# 1LFO.net
KiCad netlist of a schematic drawn in EAGLE
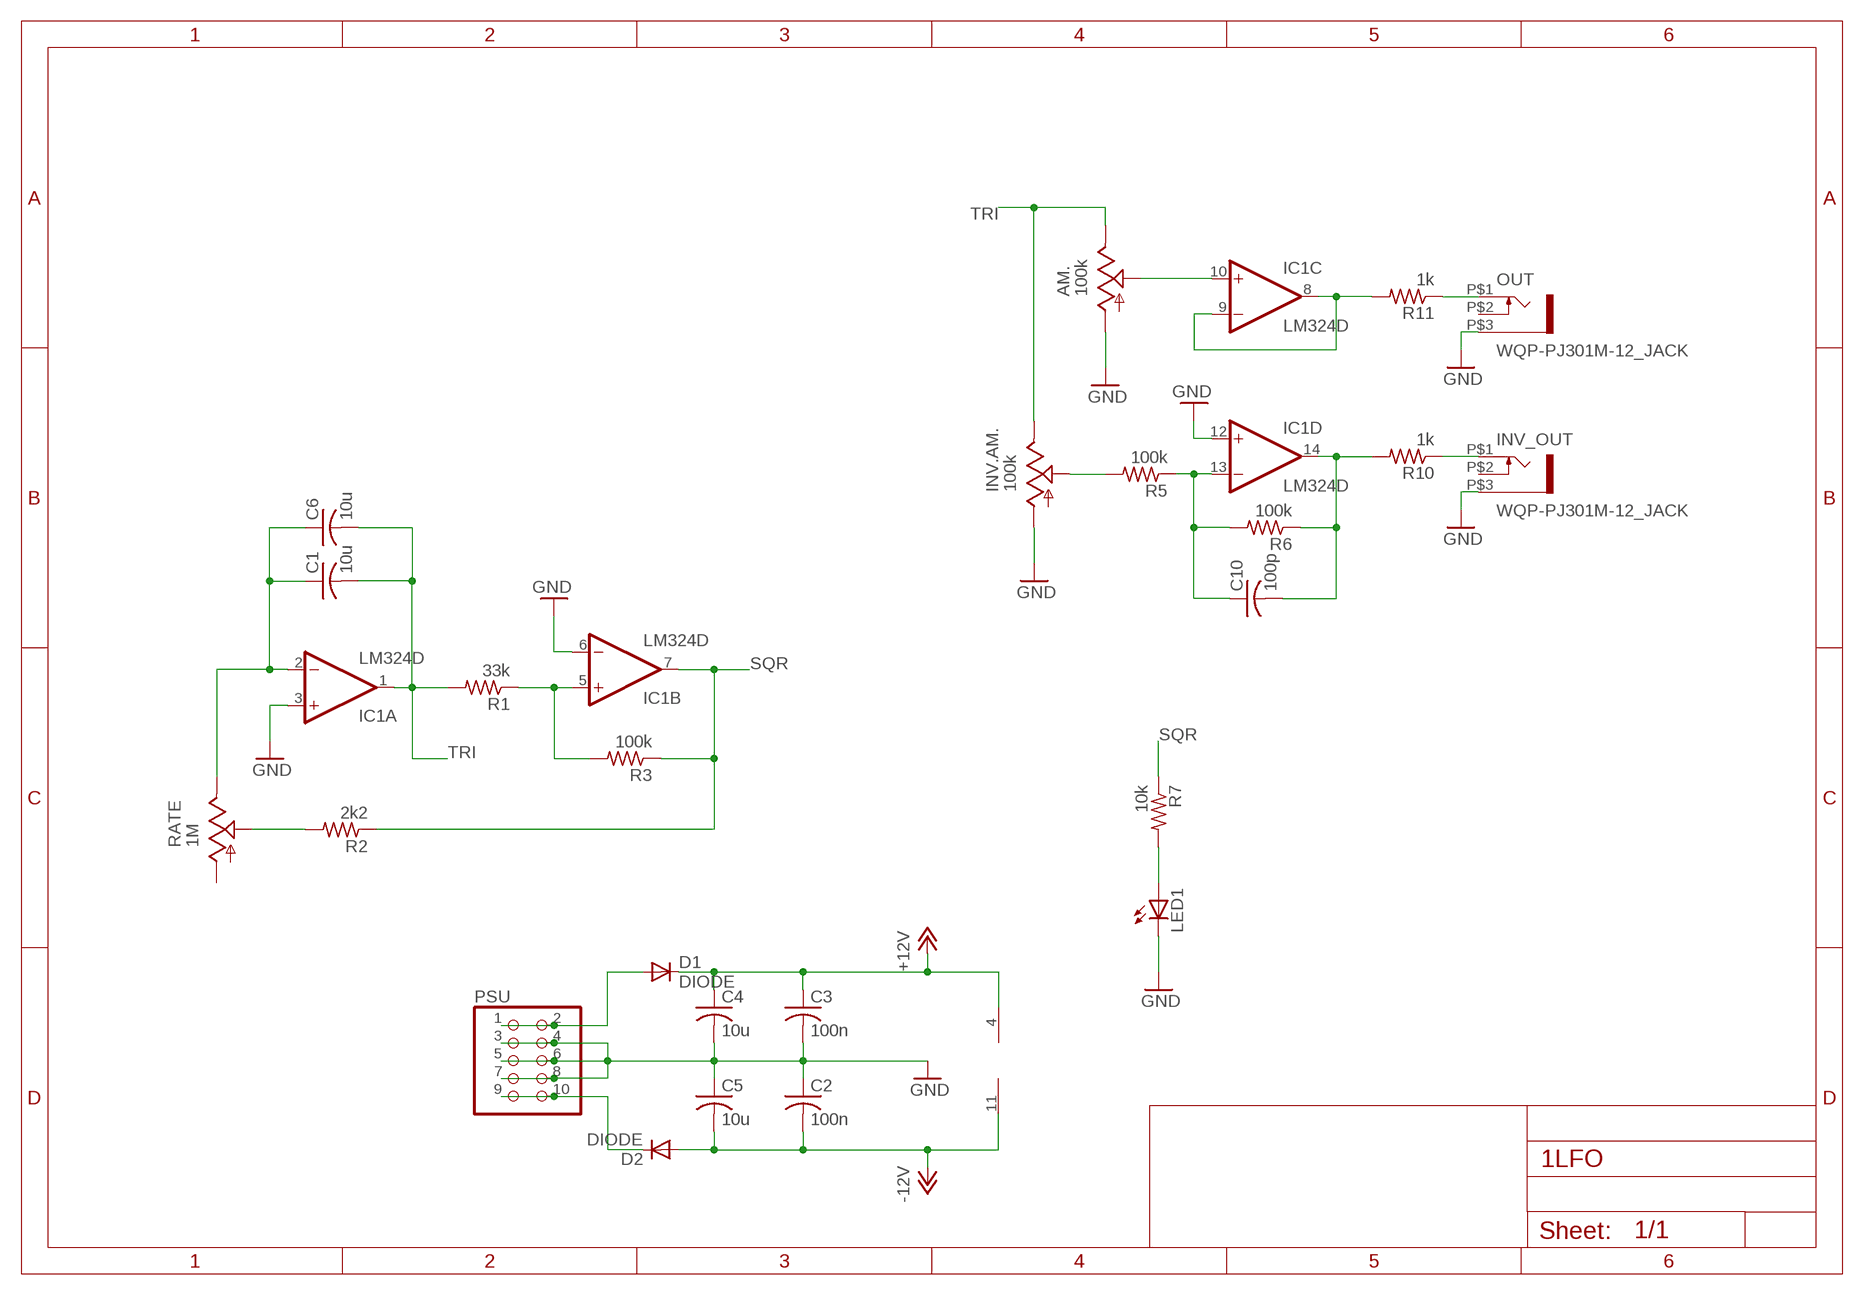
[diagram p0: schematic, sheet 1]

(export (version "E")
  (design (tool "Eeschema 10.0.6"))
  (components
    (comp (ref "AM.")
      (value "100k")
      (footprint "eagle-import:ALPS_POT_VERTICAL")
      (libsource (lib "eagle-import") (part "POT_USVERTICAL"))
    )
    (comp (ref "C1")
      (value "10u")
      (footprint "eagle-import:C1206K")
      (libsource (lib "eagle-import") (part "C-USC1206K"))
    )
    (comp (ref "C2")
      (value "100n")
      (footprint "eagle-import:C0603K")
      (libsource (lib "eagle-import") (part "C-USC0603K"))
    )
    (comp (ref "C3")
      (value "100n")
      (footprint "eagle-import:C0603K")
      (libsource (lib "eagle-import") (part "C-USC0603K"))
    )
    (comp (ref "C4")
      (value "10u")
      (footprint "eagle-import:C1206K")
      (libsource (lib "eagle-import") (part "C-USC1206K"))
    )
    (comp (ref "C5")
      (value "10u")
      (footprint "eagle-import:C1206K")
      (libsource (lib "eagle-import") (part "C-USC1206K"))
    )
    (comp (ref "C6")
      (value "10u")
      (footprint "eagle-import:C0603K")
      (libsource (lib "eagle-import") (part "C-USC0603K"))
    )
    (comp (ref "C10")
      (value "100p")
      (footprint "eagle-import:C0603K")
      (libsource (lib "eagle-import") (part "C-USC0603K"))
    )
    (comp (ref "D1")
      (value "DIODE")
      (footprint "eagle-import:DO214AA")
      (libsource (lib "eagle-import") (part "DIODE-DO214AA"))
    )
    (comp (ref "D2")
      (value "DIODE")
      (footprint "eagle-import:DO214AA")
      (libsource (lib "eagle-import") (part "DIODE-DO214AA"))
    )
    (comp (ref "IC1")
      (value "LM324D")
      (footprint "eagle-import:SO14")
      (libsource (lib "eagle-import") (part "LM324D"))
    )
    (comp (ref "INV.AM.")
      (value "100k")
      (footprint "eagle-import:ALPS_POT_VERTICAL")
      (libsource (lib "eagle-import") (part "POT_USVERTICAL"))
    )
    (comp (ref "INV_OUT")
      (value "WQP-PJ301M-12_JACK")
      (footprint "eagle-import:WQP-PJ301M-12_JACK")
      (libsource (lib "eagle-import") (part "WQP-PJ301M-12_JACK"))
    )
    (comp (ref "LED1")
      (value "LED3MM")
      (footprint "eagle-import:LED3MM")
      (libsource (lib "eagle-import") (part "LED3MM"))
    )
    (comp (ref "OUT")
      (value "WQP-PJ301M-12_JACK")
      (footprint "eagle-import:WQP-PJ301M-12_JACK")
      (libsource (lib "eagle-import") (part "WQP-PJ301M-12_JACK"))
    )
    (comp (ref "PSU")
      (value "PINHD-2X5")
      (footprint "eagle-import:2X05")
      (libsource (lib "eagle-import") (part "PINHD-2X5"))
    )
    (comp (ref "R1")
      (value "33k")
      (footprint "eagle-import:R0603")
      (libsource (lib "eagle-import") (part "R-US_R0603"))
    )
    (comp (ref "R2")
      (value "2k2")
      (footprint "eagle-import:R0603")
      (libsource (lib "eagle-import") (part "R-US_R0603"))
    )
    (comp (ref "R3")
      (value "100k")
      (footprint "eagle-import:R0603")
      (libsource (lib "eagle-import") (part "R-US_R0603"))
    )
    (comp (ref "R5")
      (value "100k")
      (footprint "eagle-import:R0603")
      (libsource (lib "eagle-import") (part "R-US_R0603"))
    )
    (comp (ref "R6")
      (value "100k")
      (footprint "eagle-import:R0603")
      (libsource (lib "eagle-import") (part "R-US_R0603"))
    )
    (comp (ref "R7")
      (value "10k")
      (footprint "eagle-import:R0603")
      (libsource (lib "eagle-import") (part "R-US_R0603"))
    )
    (comp (ref "R10")
      (value "1k")
      (footprint "eagle-import:R0603")
      (libsource (lib "eagle-import") (part "R-US_R0603"))
    )
    (comp (ref "R11")
      (value "1k")
      (footprint "eagle-import:R0603")
      (libsource (lib "eagle-import") (part "R-US_R0603"))
    )
    (comp (ref "RATE")
      (value "1M")
      (footprint "eagle-import:ALPS_POT_VERTICAL")
      (libsource (lib "eagle-import") (part "POT_USVERTICAL"))
    )
  )
  (nets
    (net (code "1") (name "+12V") (class "Default")
      (node (ref "C3") (pin "1") (pinfunction "1_1") (pintype "passive"))
      (node (ref "C4") (pin "1") (pinfunction "1_1") (pintype "passive"))
      (node (ref "D1") (pin "C") (pinfunction "C_C") (pintype "passive"))
      (node (ref "IC1") (pin "4") (pinfunction "V+_4") (pintype "power_in"))
    )
    (net (code "2") (name "-12V") (class "Default")
      (node (ref "C2") (pin "2") (pinfunction "2_2") (pintype "passive"))
      (node (ref "C5") (pin "2") (pinfunction "2_2") (pintype "passive"))
      (node (ref "D2") (pin "A") (pinfunction "A_A") (pintype "passive"))
      (node (ref "IC1") (pin "11") (pinfunction "V-_11") (pintype "power_in"))
    )
    (net (code "3") (name "/SQR") (class "Default")
      (node (ref "IC1") (pin "7") (pinfunction "OUT_7") (pintype "output"))
      (node (ref "R2") (pin "1") (pinfunction "1_1") (pintype "passive"))
      (node (ref "R3") (pin "1") (pinfunction "1_1") (pintype "passive"))
      (node (ref "R7") (pin "1") (pinfunction "1_1") (pintype "passive"))
    )
    (net (code "4") (name "/TRI") (class "Default")
      (node (ref "AM.") (pin "P$1") (pinfunction "E_P$1") (pintype "passive"))
      (node (ref "C1") (pin "2") (pinfunction "2_2") (pintype "passive"))
      (node (ref "C6") (pin "2") (pinfunction "2_2") (pintype "passive"))
      (node (ref "IC1") (pin "1") (pinfunction "OUT_1") (pintype "output"))
      (node (ref "INV.AM.") (pin "P$1") (pinfunction "E_P$1") (pintype "passive"))
      (node (ref "R1") (pin "2") (pinfunction "2_2") (pintype "passive"))
    )
    (net (code "5") (name "GND") (class "Default")
      (node (ref "AM.") (pin "P$3") (pinfunction "A_P$3") (pintype "passive"))
      (node (ref "C2") (pin "1") (pinfunction "1_1") (pintype "passive"))
      (node (ref "C3") (pin "2") (pinfunction "2_2") (pintype "passive"))
      (node (ref "C4") (pin "2") (pinfunction "2_2") (pintype "passive"))
      (node (ref "C5") (pin "1") (pinfunction "1_1") (pintype "passive"))
      (node (ref "IC1") (pin "12") (pinfunction "+IN_12") (pintype "input"))
      (node (ref "IC1") (pin "3") (pinfunction "+IN_3") (pintype "input"))
      (node (ref "IC1") (pin "6") (pinfunction "-IN_6") (pintype "input"))
      (node (ref "INV.AM.") (pin "P$3") (pinfunction "A_P$3") (pintype "passive"))
      (node (ref "INV_OUT") (pin "P$3") (pinfunction "1_P$3") (pintype "passive"))
      (node (ref "LED1") (pin "K") (pinfunction "C_K") (pintype "passive"))
      (node (ref "OUT") (pin "P$3") (pinfunction "1_P$3") (pintype "passive"))
      (node (ref "PSU") (pin "3") (pinfunction "3_3") (pintype "passive"))
      (node (ref "PSU") (pin "4") (pinfunction "4_4") (pintype "passive"))
      (node (ref "PSU") (pin "5") (pinfunction "5_5") (pintype "passive"))
      (node (ref "PSU") (pin "6") (pinfunction "6_6") (pintype "passive"))
      (node (ref "PSU") (pin "7") (pinfunction "7_7") (pintype "passive"))
      (node (ref "PSU") (pin "8") (pinfunction "8_8") (pintype "passive"))
    )
    (net (code "6") (name "Net-(AM.-S)") (class "Default")
      (node (ref "AM.") (pin "P$2") (pinfunction "S_P$2") (pintype "passive"))
      (node (ref "IC1") (pin "10") (pinfunction "+IN_10") (pintype "input"))
    )
    (net (code "7") (name "Net-(D1-PadA)") (class "Default")
      (node (ref "D1") (pin "A") (pinfunction "A_A") (pintype "passive"))
      (node (ref "PSU") (pin "1") (pinfunction "1_1") (pintype "passive"))
      (node (ref "PSU") (pin "2") (pinfunction "2_2") (pintype "passive"))
    )
    (net (code "8") (name "Net-(D2-PadC)") (class "Default")
      (node (ref "D2") (pin "C") (pinfunction "C_C") (pintype "passive"))
      (node (ref "PSU") (pin "10") (pinfunction "10_10") (pintype "passive"))
      (node (ref "PSU") (pin "9") (pinfunction "9_9") (pintype "passive"))
    )
    (net (code "9") (name "Net-(IC1A--IN)") (class "Default")
      (node (ref "C1") (pin "1") (pinfunction "1_1") (pintype "passive"))
      (node (ref "C6") (pin "1") (pinfunction "1_1") (pintype "passive"))
      (node (ref "IC1") (pin "2") (pinfunction "-IN_2") (pintype "input"))
      (node (ref "RATE") (pin "P$1") (pinfunction "E_P$1") (pintype "passive"))
    )
    (net (code "10") (name "Net-(IC1B-+IN)") (class "Default")
      (node (ref "IC1") (pin "5") (pinfunction "+IN_5") (pintype "input"))
      (node (ref "R1") (pin "1") (pinfunction "1_1") (pintype "passive"))
      (node (ref "R3") (pin "2") (pinfunction "2_2") (pintype "passive"))
    )
    (net (code "11") (name "Net-(IC1C--IN)") (class "Default")
      (node (ref "IC1") (pin "8") (pinfunction "OUT_8") (pintype "output"))
      (node (ref "IC1") (pin "9") (pinfunction "-IN_9") (pintype "input"))
      (node (ref "R11") (pin "2") (pinfunction "2_2") (pintype "passive"))
    )
    (net (code "12") (name "Net-(IC1D--IN)") (class "Default")
      (node (ref "C10") (pin "1") (pinfunction "1_1") (pintype "passive"))
      (node (ref "IC1") (pin "13") (pinfunction "-IN_13") (pintype "input"))
      (node (ref "R5") (pin "1") (pinfunction "1_1") (pintype "passive"))
      (node (ref "R6") (pin "2") (pinfunction "2_2") (pintype "passive"))
    )
    (net (code "13") (name "Net-(IC1D-OUT)") (class "Default")
      (node (ref "C10") (pin "2") (pinfunction "2_2") (pintype "passive"))
      (node (ref "IC1") (pin "14") (pinfunction "OUT_14") (pintype "output"))
      (node (ref "R10") (pin "2") (pinfunction "2_2") (pintype "passive"))
      (node (ref "R6") (pin "1") (pinfunction "1_1") (pintype "passive"))
    )
    (net (code "14") (name "Net-(INV.AM.-S)") (class "Default")
      (node (ref "INV.AM.") (pin "P$2") (pinfunction "S_P$2") (pintype "passive"))
      (node (ref "R5") (pin "2") (pinfunction "2_2") (pintype "passive"))
    )
    (net (code "15") (name "Net-(INV_OUT-2)") (class "Default")
      (node (ref "INV_OUT") (pin "P$1") (pinfunction "2_P$1") (pintype "passive"))
      (node (ref "R10") (pin "1") (pinfunction "1_1") (pintype "passive"))
    )
    (net (code "16") (name "Net-(LED1-PadA)") (class "Default")
      (node (ref "LED1") (pin "A") (pinfunction "A_A") (pintype "passive"))
      (node (ref "R7") (pin "2") (pinfunction "2_2") (pintype "passive"))
    )
    (net (code "17") (name "Net-(OUT-2)") (class "Default")
      (node (ref "OUT") (pin "P$1") (pinfunction "2_P$1") (pintype "passive"))
      (node (ref "R11") (pin "1") (pinfunction "1_1") (pintype "passive"))
    )
    (net (code "18") (name "Net-(RATE-S)") (class "Default")
      (node (ref "R2") (pin "2") (pinfunction "2_2") (pintype "passive"))
      (node (ref "RATE") (pin "P$2") (pinfunction "S_P$2") (pintype "passive"))
    )
    (net (code "19") (name "unconnected-(INV_OUT-3-PadP$2)") (class "Default")
      (node (ref "INV_OUT") (pin "P$2") (pinfunction "3_P$2") (pintype "passive"))
    )
    (net (code "20") (name "unconnected-(OUT-3-PadP$2)") (class "Default")
      (node (ref "OUT") (pin "P$2") (pinfunction "3_P$2") (pintype "passive"))
    )
    (net (code "21") (name "unconnected-(RATE-A-PadP$3)") (class "Default")
      (node (ref "RATE") (pin "P$3") (pinfunction "A_P$3") (pintype "passive"))
    )
  )
)
